# MilliToney.net
KiCad netlist of a schematic drawn in EAGLE
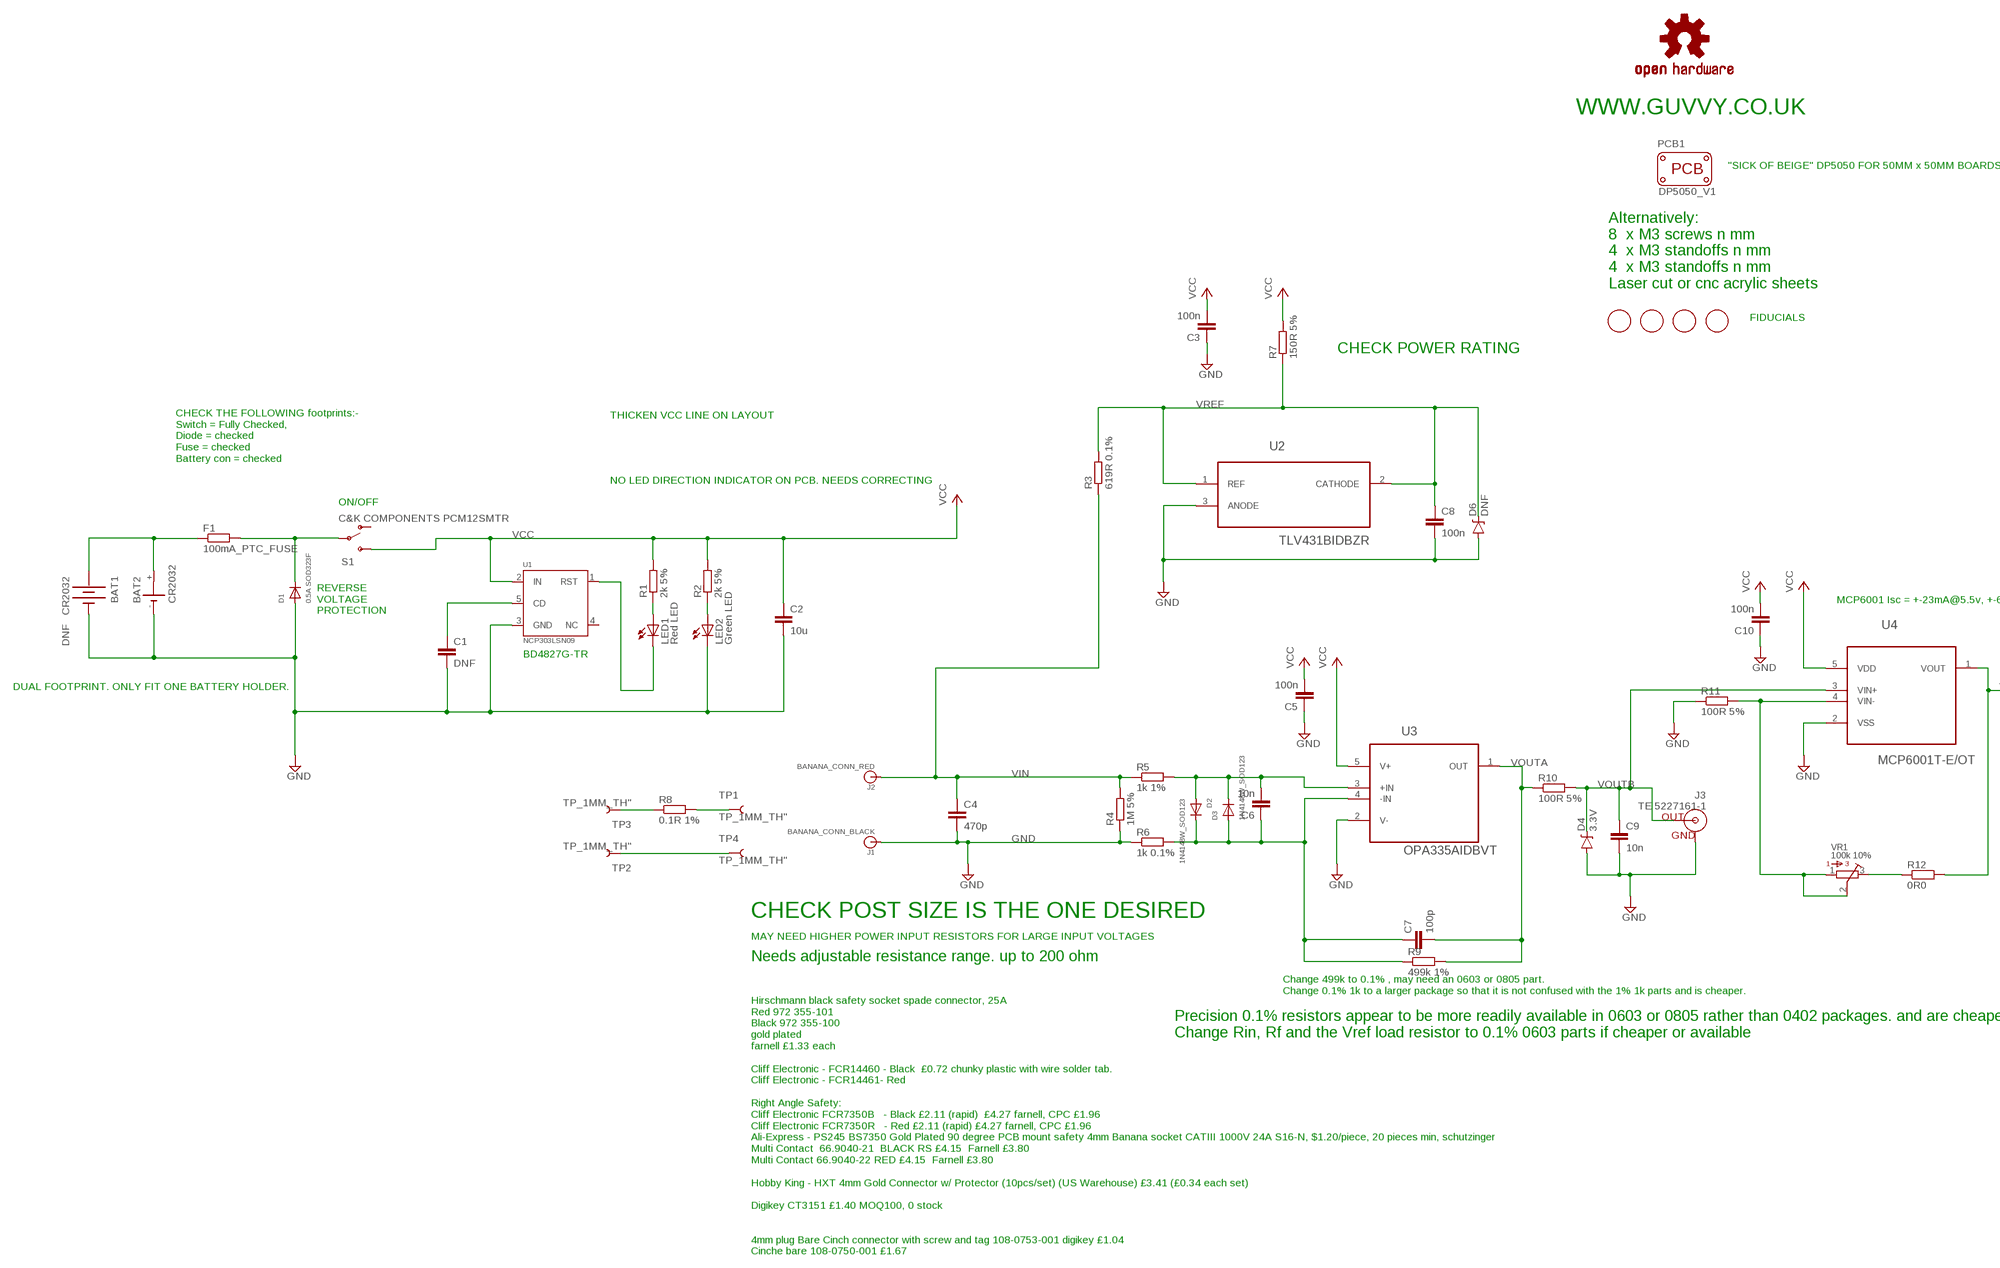
[diagram p0: schematic, sheet 1, part 1 of 2]
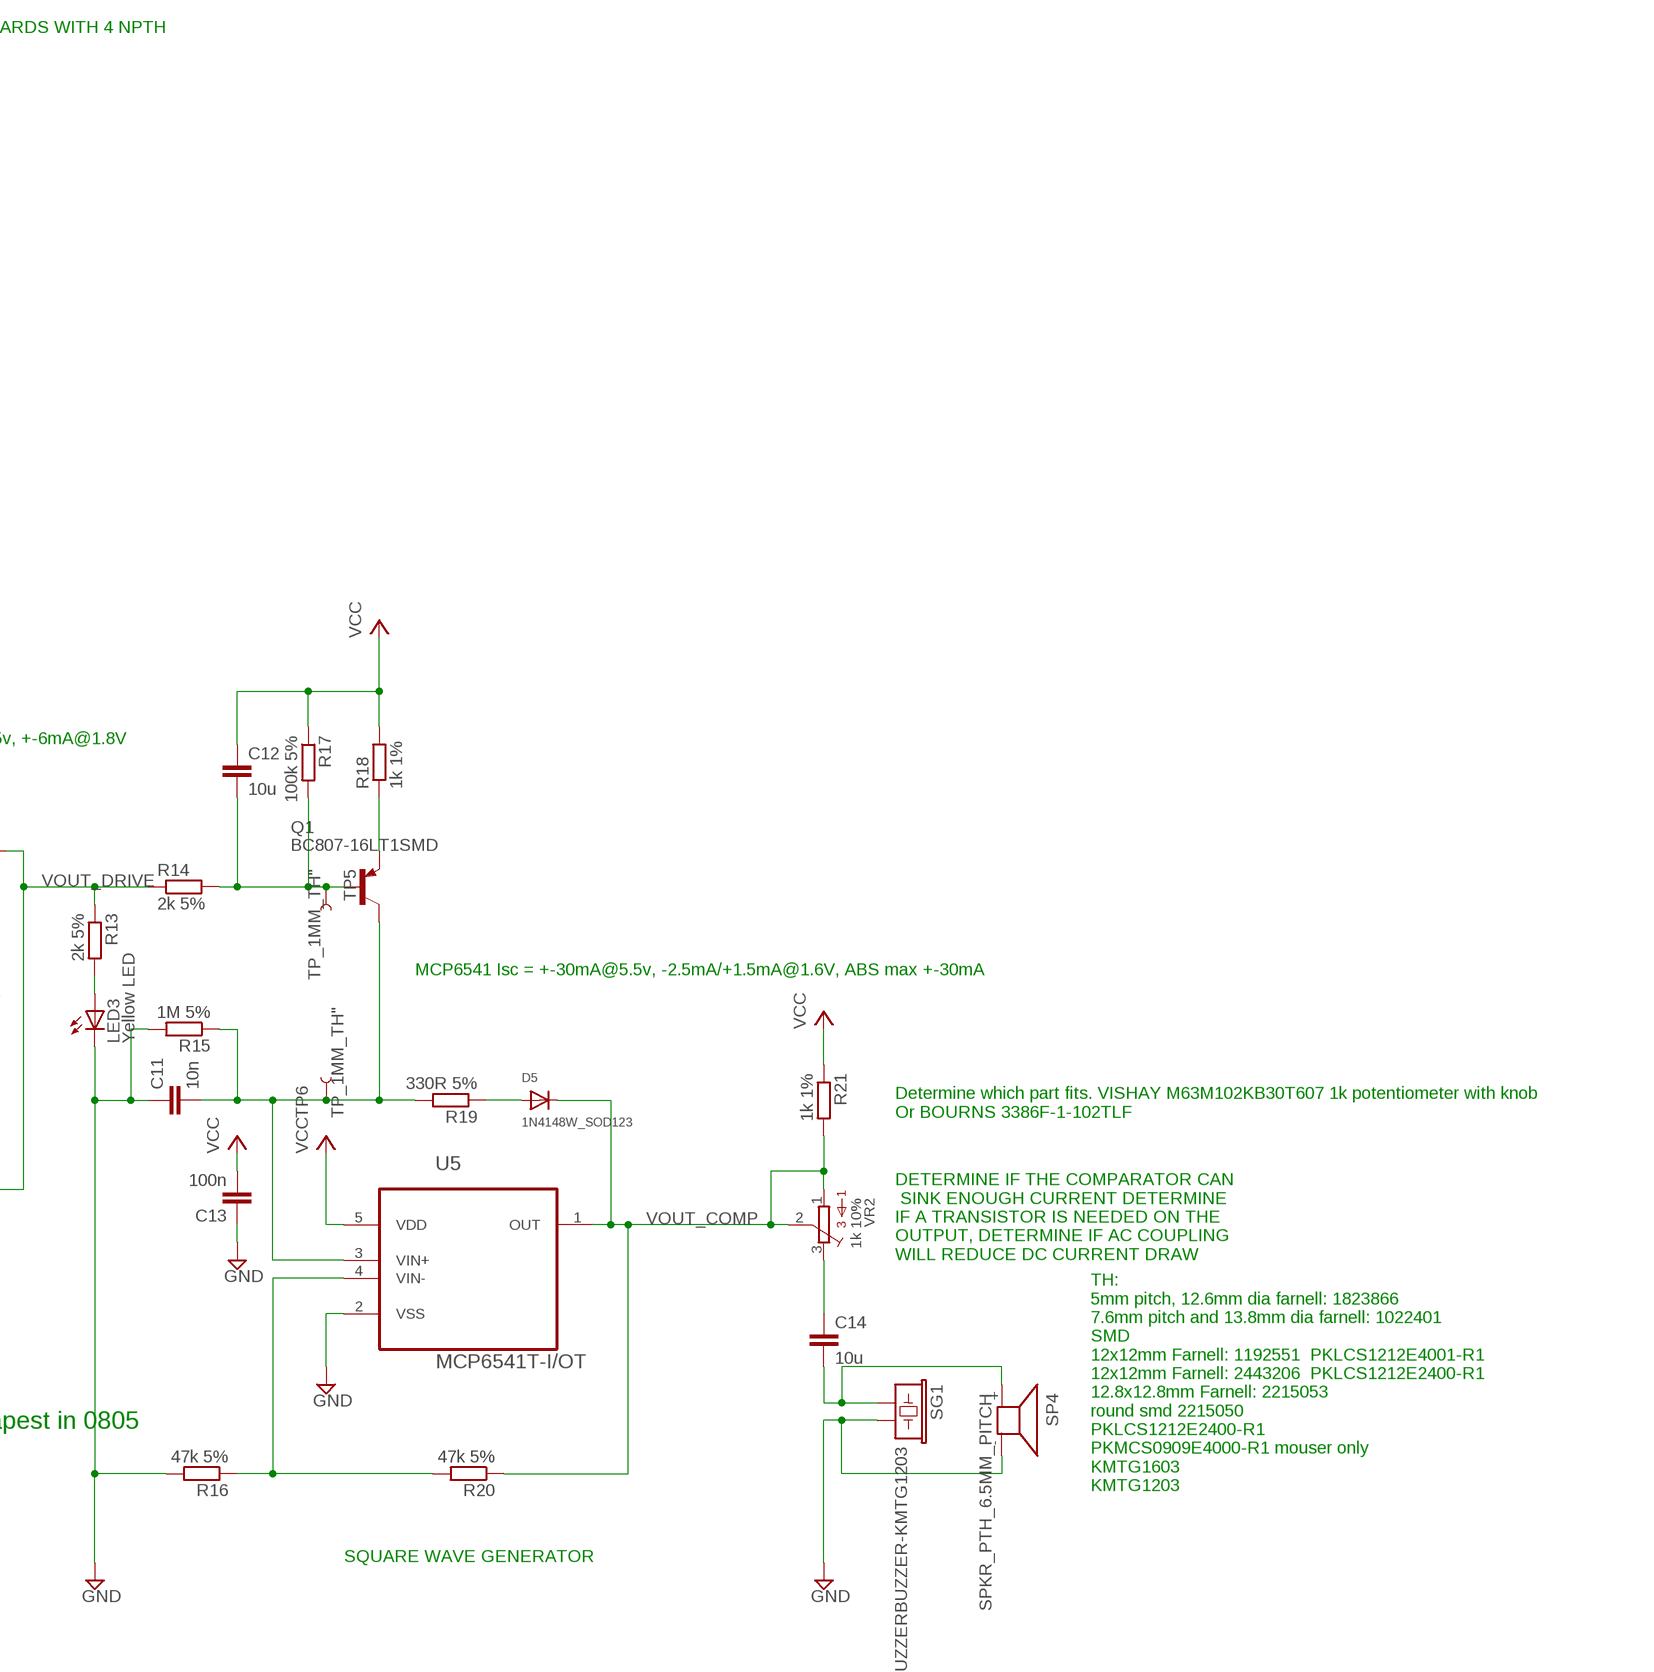
[diagram p1: schematic, sheet 1, part 2 of 2]

(export (version "E")
  (design (tool "Eeschema 10.0.6"))
  (components
    (comp (ref "BAT1")
      (value "DNF CR2032")
      (footprint "eagle-import:BATTERY_20MM_PTH_COMPACT")
      (libsource (lib "eagle-import") (part "BATTERYFOB"))
    )
    (comp (ref "BAT2")
      (value "CR2032")
      (footprint "eagle-import:KZH20SMD")
      (fields (field (name "MF") "RENATA") (field (name "MPN") "SMTU 2032-LF"))
      (libsource (lib "eagle-import") (part "2032"))
    )
    (comp (ref "C1")
      (value "DNF")
      (footprint "eagle-import:C0402K")
      (libsource (lib "eagle-import") (part "C-EUC0402K"))
    )
    (comp (ref "C2")
      (value "10u")
      (footprint "eagle-import:C0603")
      (fields (field (name "MF") "MURATA") (field (name "MPN") "GRM188R61A106ME69D"))
      (libsource (lib "eagle-import") (part "C-EUC0603"))
    )
    (comp (ref "C3")
      (value "100n")
      (footprint "eagle-import:C0402K")
      (fields (field (name "MF") "MULTICOMP") (field (name "MPN") "MC0402X104K100CT"))
      (libsource (lib "eagle-import") (part "C-EUC0402K"))
    )
    (comp (ref "C4")
      (value "470p")
      (footprint "eagle-import:C0402K")
      (libsource (lib "eagle-import") (part "C-EUC0402K"))
    )
    (comp (ref "C5")
      (value "100n")
      (footprint "eagle-import:C0402K")
      (fields (field (name "MF") "MULTICOMP") (field (name "MPN") "MC0402X104K100CT"))
      (libsource (lib "eagle-import") (part "C-EUC0402K"))
    )
    (comp (ref "C6")
      (value "10n")
      (footprint "eagle-import:C0402K")
      (libsource (lib "eagle-import") (part "C-EUC0402K"))
    )
    (comp (ref "C7")
      (value "100p")
      (footprint "eagle-import:C0402K")
      (libsource (lib "eagle-import") (part "C-EUC0402K"))
    )
    (comp (ref "C8")
      (value "100n")
      (footprint "eagle-import:C0402K")
      (fields (field (name "MF") "MULTICOMP") (field (name "MPN") "MC0402X104K100CT"))
      (libsource (lib "eagle-import") (part "C-EUC0402K"))
    )
    (comp (ref "C9")
      (value "10n")
      (footprint "eagle-import:C0402K")
      (libsource (lib "eagle-import") (part "C-EUC0402K"))
    )
    (comp (ref "C10")
      (value "100n")
      (footprint "eagle-import:C0402K")
      (fields (field (name "MF") "MULTICOMP") (field (name "MPN") "MC0402X104K100CT"))
      (libsource (lib "eagle-import") (part "C-EUC0402K"))
    )
    (comp (ref "C11")
      (value "10n")
      (footprint "eagle-import:C0402K")
      (libsource (lib "eagle-import") (part "C-EUC0402K"))
    )
    (comp (ref "C12")
      (value "10u")
      (footprint "eagle-import:C0603")
      (fields (field (name "MF") "MURATA") (field (name "MPN") "GRM188R61A106ME69D"))
      (libsource (lib "eagle-import") (part "C-EUC0603"))
    )
    (comp (ref "C13")
      (value "100n")
      (footprint "eagle-import:C0402K")
      (fields (field (name "MF") "MULTICOMP") (field (name "MPN") "MC0402X104K100CT"))
      (libsource (lib "eagle-import") (part "C-EUC0402K"))
    )
    (comp (ref "C14")
      (value "10u")
      (footprint "eagle-import:C0603K")
      (fields (field (name "MF") "MURATA") (field (name "MPN") "GRM188R61A106ME69D"))
      (libsource (lib "eagle-import") (part "C-EUC0603K"))
    )
    (comp (ref "D1")
      (value "0.5A SOD323F")
      (footprint "eagle-import:SOD-323F")
      (fields (field (name "MF") "NXP") (field (name "MPN") "PMEG3010EJ,115"))
      (libsource (lib "eagle-import") (part "DIODESOD-323F"))
    )
    (comp (ref "D2")
      (value "1N4148W_SOD123")
      (footprint "eagle-import:SOD-123FL")
      (fields (field (name "MF") "MULTICOMP") (field (name "MPN") "1N4148W"))
      (libsource (lib "eagle-import") (part "DIODE_SOD-123FL"))
    )
    (comp (ref "D3")
      (value "1N4148W_SOD123")
      (footprint "eagle-import:SOD-123FL")
      (fields (field (name "MF") "MULTICOMP") (field (name "MPN") "1N4148W"))
      (libsource (lib "eagle-import") (part "DIODE_SOD-123FL"))
    )
    (comp (ref "D4")
      (value "3.3V")
      (footprint "eagle-import:SOD-323")
      (libsource (lib "eagle-import") (part "DIODE-ZENER3.3V"))
    )
    (comp (ref "D5")
      (value "1N4148W_SOD123")
      (footprint "eagle-import:SOD-123FL")
      (fields (field (name "MF") "MULTICOMP") (field (name "MPN") "1N4148W"))
      (libsource (lib "eagle-import") (part "DIODE_SOD-123FL"))
    )
    (comp (ref "D6")
      (value "DNF")
      (footprint "eagle-import:SOD-323")
      (libsource (lib "eagle-import") (part "DIODE-ZENER3.3V"))
    )
    (comp (ref "F1")
      (value "100mA_PTC_FUSE")
      (footprint "eagle-import:R0805")
      (fields (field (name "MF") "BOURNS") (field (name "MPN") "MF-PSMF010X-2"))
      (libsource (lib "eagle-import") (part "R-EU_R0805"))
    )
    (comp (ref "FID1")
      (value "FIDUCIAL")
      (footprint "eagle-import:FIDUCIAL_1MM")
      (libsource (lib "eagle-import") (part "FIDUCIAL"))
    )
    (comp (ref "FID2")
      (value "FIDUCIAL")
      (footprint "eagle-import:FIDUCIAL_1MM")
      (libsource (lib "eagle-import") (part "FIDUCIAL"))
    )
    (comp (ref "FID3")
      (value "FIDUCIAL")
      (footprint "eagle-import:FIDUCIAL_1MM")
      (libsource (lib "eagle-import") (part "FIDUCIAL"))
    )
    (comp (ref "FID4")
      (value "FIDUCIAL")
      (footprint "eagle-import:FIDUCIAL_1MM")
      (libsource (lib "eagle-import") (part "FIDUCIAL"))
    )
    (comp (ref "J1")
      (value "BANANA_CONN_BLACK")
      (footprint "eagle-import:BANANA_CONN")
      (fields (field (name "MF") "CLIFF ELECTRONIC COMPONENTS") (field (name "MPN") "FCR14460"))
      (libsource (lib "eagle-import") (part "BANANA_CONN"))
    )
    (comp (ref "J2")
      (value "BANANA_CONN_RED")
      (footprint "eagle-import:BANANA_CONN")
      (fields (field (name "MF") "CLIFF ELECTRONIC COMPONENTS") (field (name "MPN") "FCR14461"))
      (libsource (lib "eagle-import") (part "BANANA_CONN"))
    )
    (comp (ref "J3")
      (value "TE 5227161-1")
      (footprint "eagle-import:BNC")
      (fields (field (name "MF") "TE CONNECTIVITY / AMP") (field (name "MPN") "5227161-1"))
      (libsource (lib "eagle-import") (part "BNCPTH"))
    )
    (comp (ref "LED1")
      (value "Red LED")
      (footprint "eagle-import:SML0603")
      (fields (field (name "MF") "KINGBRIGHT") (field (name "MPN") "KP-1608SURCK"))
      (libsource (lib "eagle-import") (part "LEDSML0603"))
    )
    (comp (ref "LED2")
      (value "Green LED")
      (footprint "eagle-import:SML0603")
      (fields (field (name "MF") "KINGBRIGHT") (field (name "MPN") "KP-1608CGCK"))
      (libsource (lib "eagle-import") (part "LEDSML0603"))
    )
    (comp (ref "LED3")
      (value "Yellow LED")
      (footprint "eagle-import:SML0603")
      (fields (field (name "MF") "KINGBRIGHT") (field (name "MPN") "KP-1608SYCK"))
      (libsource (lib "eagle-import") (part "LEDSML0603"))
    )
    (comp (ref "LOGO1")
      (value "OSHW-LOGOL")
      (footprint "eagle-import:OSHW-LOGO-L")
      (libsource (lib "eagle-import") (part "OSHW-LOGOL"))
    )
    (comp (ref "PCB1")
      (value "PCB_DP_SQUARE-5X5")
      (footprint "eagle-import:DP5050_V1")
      (libsource (lib "eagle-import") (part "PCB_DP_SQUARE-5X5"))
    )
    (comp (ref "Q1")
      (value "BC807-16LT1SMD")
      (footprint "eagle-import:SOT23-BEC")
      (fields (field (name "MF") "ON SEMICONDUCTOR") (field (name "MPN") "BC807-16LT1G"))
      (libsource (lib "eagle-import") (part "BC807SMD-16LT1"))
    )
    (comp (ref "R1")
      (value "2k 5%")
      (footprint "eagle-import:R0402")
      (libsource (lib "eagle-import") (part "R-EU_R0402"))
    )
    (comp (ref "R2")
      (value "2k 5%")
      (footprint "eagle-import:R0402")
      (libsource (lib "eagle-import") (part "R-EU_R0402"))
    )
    (comp (ref "R3")
      (value "619R 0.1%")
      (footprint "eagle-import:R0402")
      (fields (field (name "MF") "TE CONNECTIVITY") (field (name "MPN") "CPF0402B619RE1"))
      (libsource (lib "eagle-import") (part "R-EU_R0402"))
    )
    (comp (ref "R4")
      (value "1M 5%")
      (footprint "eagle-import:R0402")
      (libsource (lib "eagle-import") (part "R-EU_R0402"))
    )
    (comp (ref "R5")
      (value "1k 1%")
      (footprint "eagle-import:R0402")
      (libsource (lib "eagle-import") (part "R-EU_R0402"))
    )
    (comp (ref "R6")
      (value "1k 0.1%")
      (footprint "eagle-import:R0402")
      (fields (field (name "MF") "WELWYN") (field (name "MPN") "PCF0402-R-1K-B-T1."))
      (libsource (lib "eagle-import") (part "R-EU_R0402"))
    )
    (comp (ref "R7")
      (value "150R 5%")
      (footprint "eagle-import:R0402")
      (libsource (lib "eagle-import") (part "R-EU_R0402"))
    )
    (comp (ref "R8")
      (value "0.1R 1%")
      (footprint "eagle-import:R0603")
      (fields (field (name "MF") "PANASONIC ELECTRONIC COMPONENTS") (field (name "MPN") "ERJ3RSFR10V"))
      (libsource (lib "eagle-import") (part "R-EU_R0603"))
    )
    (comp (ref "R9")
      (value "499k 1%")
      (footprint "eagle-import:R0402")
      (fields (field (name "MF") "PANASONIC ELECTRONIC COMPONENTS") (field (name "MPN") "ERJ3EKF4993V"))
      (libsource (lib "eagle-import") (part "R-EU_R0402"))
    )
    (comp (ref "R10")
      (value "100R 5%")
      (footprint "eagle-import:R0402")
      (libsource (lib "eagle-import") (part "R-EU_R0402"))
    )
    (comp (ref "R11")
      (value "100R 5%")
      (footprint "eagle-import:R0402")
      (libsource (lib "eagle-import") (part "R-EU_R0402"))
    )
    (comp (ref "R12")
      (value "0R0")
      (footprint "eagle-import:R0402")
      (libsource (lib "eagle-import") (part "R-EU_R0402"))
    )
    (comp (ref "R13")
      (value "2k 5%")
      (footprint "eagle-import:R0402")
      (libsource (lib "eagle-import") (part "R-EU_R0402"))
    )
    (comp (ref "R14")
      (value "2k 5%")
      (footprint "eagle-import:R0402")
      (libsource (lib "eagle-import") (part "R-EU_R0402"))
    )
    (comp (ref "R15")
      (value "1M 5%")
      (footprint "eagle-import:R0402")
      (libsource (lib "eagle-import") (part "R-EU_R0402"))
    )
    (comp (ref "R16")
      (value "47k 5%")
      (footprint "eagle-import:R0402")
      (libsource (lib "eagle-import") (part "R-EU_R0402"))
    )
    (comp (ref "R17")
      (value "100k 5%")
      (footprint "eagle-import:R0402")
      (libsource (lib "eagle-import") (part "R-EU_R0402"))
    )
    (comp (ref "R18")
      (value "1k 1%")
      (footprint "eagle-import:R0402")
      (libsource (lib "eagle-import") (part "R-EU_R0402"))
    )
    (comp (ref "R19")
      (value "330R 5%")
      (footprint "eagle-import:R0402")
      (libsource (lib "eagle-import") (part "R-EU_R0402"))
    )
    (comp (ref "R20")
      (value "47k 5%")
      (footprint "eagle-import:R0402")
      (libsource (lib "eagle-import") (part "R-EU_R0402"))
    )
    (comp (ref "R21")
      (value "1k 1%")
      (footprint "eagle-import:R0402")
      (libsource (lib "eagle-import") (part "R-EU_R0402"))
    )
    (comp (ref "S1")
      (value "C&K COMPONENTS PCM12SMTR")
      (footprint "eagle-import:SWITCH-SPST-SMD-A")
      (fields (field (name "MF") "C & K COMPONENTS") (field (name "MPN") "PCM12SMTR"))
      (libsource (lib "eagle-import") (part "SWITCH-SPDT-SMD-A"))
    )
    (comp (ref "SG1")
      (value "BUZZERBUZZER-KMTG1203")
      (footprint "eagle-import:BUZZER-KMTG1203")
      (fields (field (name "MF") "KINGSTATE") (field (name "MPN") "KMTG1203"))
      (libsource (lib "eagle-import") (part "BUZZERBUZZER-KMTG1203"))
    )
    (comp (ref "SP4")
      (value "SPKR_PTH_6.5MM_PITCH")
      (footprint "eagle-import:KSS1201")
      (libsource (lib "eagle-import") (part "KSS1201"))
    )
    (comp (ref "TP1")
      (value "TP_1MM_TH\"")
      (footprint "eagle-import:TP_1MM_TH")
      (libsource (lib "eagle-import") (part "TP_1MM_TH{dblquote}"))
    )
    (comp (ref "TP2")
      (value "TP_1MM_TH\"")
      (footprint "eagle-import:TP_1MM_TH")
      (libsource (lib "eagle-import") (part "TP_1MM_TH{dblquote}"))
    )
    (comp (ref "TP3")
      (value "TP_1MM_TH\"")
      (footprint "eagle-import:TP_1MM_TH")
      (libsource (lib "eagle-import") (part "TP_1MM_TH{dblquote}"))
    )
    (comp (ref "TP4")
      (value "TP_1MM_TH\"")
      (footprint "eagle-import:TP_1MM_TH")
      (libsource (lib "eagle-import") (part "TP_1MM_TH{dblquote}"))
    )
    (comp (ref "TP5")
      (value "TP_1MM_TH\"")
      (footprint "eagle-import:TP_1MM_TH")
      (libsource (lib "eagle-import") (part "TP_1MM_TH{dblquote}"))
    )
    (comp (ref "TP6")
      (value "TP_1MM_TH\"")
      (footprint "eagle-import:TP_1MM_TH")
      (libsource (lib "eagle-import") (part "TP_1MM_TH{dblquote}"))
    )
    (comp (ref "U1")
      (value "NCP303LSN09")
      (footprint "eagle-import:SOT23-5")
      (fields (field (name "MF") "ROHM") (field (name "MPN") "BD4827G-TR"))
      (libsource (lib "eagle-import") (part "NCP303LSN09"))
    )
    (comp (ref "U2")
      (value "TLV431BIDBZR")
      (footprint "eagle-import:SOT95P237X112-3N")
      (fields
        (field (name "MF") "TEXAS INSTRUMENTS")
        (field (name "MPN") "TLV431BCDBZTG4")
        (field (name "OC_FARNELL") "1053385")
      )
      (libsource (lib "eagle-import") (part "TLV431BIDBZR"))
    )
    (comp (ref "U3")
      (value "OPA335AIDBVT")
      (footprint "eagle-import:SOT95P280X145-5N")
      (fields (field (name "MF") "TEXAS INSTRUMENTS"))
      (libsource (lib "eagle-import") (part "OPA335AIDBVT"))
    )
    (comp (ref "U4")
      (value "MCP6001T-E/OT")
      (footprint "eagle-import:SOT95P270X145-5N")
      (fields (field (name "MF") "MICROCHIP"))
      (libsource (lib "eagle-import") (part "MCP6001T-E/OT"))
    )
    (comp (ref "U5")
      (value "MCP6541T-I/OT")
      (footprint "eagle-import:SOT95P290X145-5N")
      (fields (field (name "MF") "MICROCHIP"))
      (libsource (lib "eagle-import") (part "MCP6541T-I/OT"))
    )
    (comp (ref "VR1")
      (value "100k 10%")
      (footprint "eagle-import:3386F")
      (fields (field (name "MF") "BOURNS") (field (name "MPN") "3386F-1-104TLF"))
      (libsource (lib "eagle-import") (part "3386-F"))
    )
    (comp (ref "VR2")
      (value "1k 10%")
      (footprint "eagle-import:3386F")
      (fields (field (name "MF") "BOURNS") (field (name "MPN") "3386F-1-102TLF"))
      (libsource (lib "eagle-import") (part "3386-F"))
    )
  )
  (nets
    (net (code "1") (name "/VIN") (class "Default")
      (node (ref "C4") (pin "1") (pinfunction "1_1") (pintype "passive"))
      (node (ref "J2") (pin "P$1") (pinfunction "1_P$1") (pintype "passive"))
      (node (ref "R3") (pin "1") (pinfunction "1_1") (pintype "passive"))
      (node (ref "R4") (pin "2") (pinfunction "2_2") (pintype "passive"))
      (node (ref "R5") (pin "1") (pinfunction "1_1") (pintype "passive"))
    )
    (net (code "2") (name "/VOUTA") (class "Default")
      (node (ref "C7") (pin "2") (pinfunction "2_2") (pintype "passive"))
      (node (ref "R10") (pin "1") (pinfunction "1_1") (pintype "passive"))
      (node (ref "R9") (pin "2") (pinfunction "2_2") (pintype "passive"))
      (node (ref "U3") (pin "1") (pinfunction "OUT_1") (pintype "output"))
    )
    (net (code "3") (name "/VOUTB") (class "Default")
      (node (ref "C9") (pin "1") (pinfunction "1_1") (pintype "passive"))
      (node (ref "D4") (pin "C") (pinfunction "C_C") (pintype "passive"))
      (node (ref "J3") (pin "S") (pinfunction "OUT_S") (pintype "bidirectional"))
      (node (ref "R10") (pin "2") (pinfunction "2_2") (pintype "passive"))
      (node (ref "U4") (pin "3") (pinfunction "VIN+_3") (pintype "input"))
    )
    (net (code "4") (name "/VOUT_COMP") (class "Default")
      (node (ref "D5") (pin "C") (pinfunction "C_C") (pintype "passive"))
      (node (ref "R20") (pin "1") (pinfunction "1_1") (pintype "passive"))
      (node (ref "R21") (pin "2") (pinfunction "2_2") (pintype "passive"))
      (node (ref "U5") (pin "1") (pinfunction "OUT_1") (pintype "output"))
      (node (ref "VR2") (pin "1") (pinfunction "1_1") (pintype "passive"))
      (node (ref "VR2") (pin "2") (pinfunction "2_2") (pintype "passive"))
    )
    (net (code "5") (name "/VOUT_DRIVE") (class "Default")
      (node (ref "R12") (pin "2") (pinfunction "2_2") (pintype "passive"))
      (node (ref "R13") (pin "1") (pinfunction "1_1") (pintype "passive"))
      (node (ref "R14") (pin "1") (pinfunction "1_1") (pintype "passive"))
      (node (ref "U4") (pin "1") (pinfunction "VOUT_1") (pintype "output"))
    )
    (net (code "6") (name "/VREF") (class "Default")
      (node (ref "C8") (pin "1") (pinfunction "1_1") (pintype "passive"))
      (node (ref "D6") (pin "C") (pinfunction "C_C") (pintype "passive"))
      (node (ref "R3") (pin "2") (pinfunction "2_2") (pintype "passive"))
      (node (ref "R7") (pin "1") (pinfunction "1_1") (pintype "passive"))
      (node (ref "U2") (pin "1") (pinfunction "REF_1") (pintype "passive"))
      (node (ref "U2") (pin "2") (pinfunction "CATHODE_2") (pintype "output"))
    )
    (net (code "7") (name "GND") (class "Default")
      (node (ref "BAT1") (pin "2") (pinfunction "-_2") (pintype "power_in"))
      (node (ref "BAT2") (pin "-") (pinfunction "-_-") (pintype "passive"))
      (node (ref "C1") (pin "2") (pinfunction "2_2") (pintype "passive"))
      (node (ref "C10") (pin "1") (pinfunction "1_1") (pintype "passive"))
      (node (ref "C11") (pin "1") (pinfunction "1_1") (pintype "passive"))
      (node (ref "C13") (pin "1") (pinfunction "1_1") (pintype "passive"))
      (node (ref "C2") (pin "2") (pinfunction "2_2") (pintype "passive"))
      (node (ref "C3") (pin "1") (pinfunction "1_1") (pintype "passive"))
      (node (ref "C4") (pin "2") (pinfunction "2_2") (pintype "passive"))
      (node (ref "C5") (pin "1") (pinfunction "1_1") (pintype "passive"))
      (node (ref "C8") (pin "2") (pinfunction "2_2") (pintype "passive"))
      (node (ref "C9") (pin "2") (pinfunction "2_2") (pintype "passive"))
      (node (ref "D1") (pin "A") (pinfunction "A_A") (pintype "passive"))
      (node (ref "D4") (pin "A") (pinfunction "A_A") (pintype "passive"))
      (node (ref "D6") (pin "A") (pinfunction "A_A") (pintype "passive"))
      (node (ref "J1") (pin "P$1") (pinfunction "1_P$1") (pintype "passive"))
      (node (ref "J3") (pin "GND") (pinfunction "GND_GND") (pintype "bidirectional"))
      (node (ref "LED2") (pin "C") (pinfunction "C_C") (pintype "passive"))
      (node (ref "LED3") (pin "C") (pinfunction "C_C") (pintype "passive"))
      (node (ref "R11") (pin "1") (pinfunction "1_1") (pintype "passive"))
      (node (ref "R15") (pin "2") (pinfunction "2_2") (pintype "passive"))
      (node (ref "R16") (pin "2") (pinfunction "2_2") (pintype "passive"))
      (node (ref "R4") (pin "1") (pinfunction "1_1") (pintype "passive"))
      (node (ref "R6") (pin "1") (pinfunction "1_1") (pintype "passive"))
      (node (ref "SG1") (pin "2") (pinfunction "2_2") (pintype "passive"))
      (node (ref "SP4") (pin "-") (pinfunction "2_-") (pintype "passive"))
      (node (ref "U1") (pin "3") (pinfunction "GND_3") (pintype "bidirectional"))
      (node (ref "U2") (pin "3") (pinfunction "ANODE_3") (pintype "input"))
      (node (ref "U3") (pin "2") (pinfunction "V-_2") (pintype "power_in"))
      (node (ref "U4") (pin "2") (pinfunction "VSS_2") (pintype "passive"))
      (node (ref "U5") (pin "2") (pinfunction "VSS_2") (pintype "power_in"))
    )
    (net (code "8") (name "Net-(BAT1-+)") (class "Default")
      (node (ref "BAT1") (pin "1") (pinfunction "+_1") (pintype "power_in"))
      (node (ref "BAT2") (pin "+") (pinfunction "+_+") (pintype "passive"))
      (node (ref "F1") (pin "1") (pinfunction "1_1") (pintype "passive"))
    )
    (net (code "9") (name "Net-(C14-Pad1)") (class "Default")
      (node (ref "C14") (pin "1") (pinfunction "1_1") (pintype "passive"))
      (node (ref "VR2") (pin "3") (pinfunction "3_3") (pintype "passive"))
    )
    (net (code "10") (name "Net-(D5-PadA)") (class "Default")
      (node (ref "D5") (pin "A") (pinfunction "A_A") (pintype "passive"))
      (node (ref "R19") (pin "1") (pinfunction "1_1") (pintype "passive"))
    )
    (net (code "11") (name "Net-(LED1-PadA)") (class "Default")
      (node (ref "LED1") (pin "A") (pinfunction "A_A") (pintype "passive"))
      (node (ref "R1") (pin "1") (pinfunction "1_1") (pintype "passive"))
    )
    (net (code "12") (name "Net-(LED2-PadA)") (class "Default")
      (node (ref "LED2") (pin "A") (pinfunction "A_A") (pintype "passive"))
      (node (ref "R2") (pin "1") (pinfunction "1_1") (pintype "passive"))
    )
    (net (code "13") (name "Net-(LED3-PadA)") (class "Default")
      (node (ref "LED3") (pin "A") (pinfunction "A_A") (pintype "passive"))
      (node (ref "R13") (pin "2") (pinfunction "2_2") (pintype "passive"))
    )
    (net (code "14") (name "Net-(Q1-PadE)") (class "Default")
      (node (ref "Q1") (pin "E") (pinfunction "E_E") (pintype "passive"))
      (node (ref "R18") (pin "1") (pinfunction "1_1") (pintype "passive"))
    )
    (net (code "15") (name "Net-(R12-Pad1)") (class "Default")
      (node (ref "R12") (pin "1") (pinfunction "1_1") (pintype "passive"))
      (node (ref "VR1") (pin "3") (pinfunction "3_3") (pintype "passive"))
    )
    (net (code "16") (name "Net-(S1-P)") (class "Default")
      (node (ref "D1") (pin "C") (pinfunction "C_C") (pintype "passive"))
      (node (ref "F1") (pin "2") (pinfunction "2_2") (pintype "passive"))
      (node (ref "S1") (pin "2") (pinfunction "P_2") (pintype "passive"))
    )
    (net (code "17") (name "Net-(SP4-1)") (class "Default")
      (node (ref "C14") (pin "2") (pinfunction "2_2") (pintype "passive"))
      (node (ref "SG1") (pin "1") (pinfunction "1_1") (pintype "passive"))
      (node (ref "SP4") (pin "+") (pinfunction "1_+") (pintype "passive"))
    )
    (net (code "18") (name "Net-(TP1-1)") (class "Default")
      (node (ref "R8") (pin "2") (pinfunction "2_2") (pintype "passive"))
      (node (ref "TP1") (pin "P$1") (pinfunction "1_P$1") (pintype "bidirectional"))
    )
    (net (code "19") (name "Net-(TP2-1)") (class "Default")
      (node (ref "TP2") (pin "P$1") (pinfunction "1_P$1") (pintype "bidirectional"))
      (node (ref "TP4") (pin "P$1") (pinfunction "1_P$1") (pintype "bidirectional"))
    )
    (net (code "20") (name "Net-(TP3-1)") (class "Default")
      (node (ref "R8") (pin "1") (pinfunction "1_1") (pintype "passive"))
      (node (ref "TP3") (pin "P$1") (pinfunction "1_P$1") (pintype "bidirectional"))
    )
    (net (code "21") (name "Net-(TP5-1)") (class "Default")
      (node (ref "C12") (pin "2") (pinfunction "2_2") (pintype "passive"))
      (node (ref "Q1") (pin "B") (pinfunction "B_B") (pintype "passive"))
      (node (ref "R14") (pin "2") (pinfunction "2_2") (pintype "passive"))
      (node (ref "R17") (pin "2") (pinfunction "2_2") (pintype "passive"))
      (node (ref "TP5") (pin "P$1") (pinfunction "1_P$1") (pintype "bidirectional"))
    )
    (net (code "22") (name "Net-(TP6-1)") (class "Default")
      (node (ref "C11") (pin "2") (pinfunction "2_2") (pintype "passive"))
      (node (ref "Q1") (pin "C") (pinfunction "C_C") (pintype "passive"))
      (node (ref "R15") (pin "1") (pinfunction "1_1") (pintype "passive"))
      (node (ref "R19") (pin "2") (pinfunction "2_2") (pintype "passive"))
      (node (ref "TP6") (pin "P$1") (pinfunction "1_P$1") (pintype "bidirectional"))
      (node (ref "U5") (pin "3") (pinfunction "VIN+_3") (pintype "input"))
    )
    (net (code "23") (name "Net-(U1-CD)") (class "Default")
      (node (ref "C1") (pin "1") (pinfunction "1_1") (pintype "passive"))
      (node (ref "U1") (pin "5") (pinfunction "CD_5") (pintype "bidirectional"))
    )
    (net (code "24") (name "Net-(U1-RST)") (class "Default")
      (node (ref "LED1") (pin "C") (pinfunction "C_C") (pintype "passive"))
      (node (ref "U1") (pin "1") (pinfunction "RST_1") (pintype "bidirectional"))
    )
    (net (code "25") (name "Net-(U3-+IN)") (class "Default")
      (node (ref "C6") (pin "2") (pinfunction "2_2") (pintype "passive"))
      (node (ref "D2") (pin "A") (pinfunction "A_A") (pintype "passive"))
      (node (ref "D3") (pin "C") (pinfunction "C_C") (pintype "passive"))
      (node (ref "R5") (pin "2") (pinfunction "2_2") (pintype "passive"))
      (node (ref "U3") (pin "3") (pinfunction "+IN_3") (pintype "input"))
    )
    (net (code "26") (name "Net-(U3--IN)") (class "Default")
      (node (ref "C6") (pin "1") (pinfunction "1_1") (pintype "passive"))
      (node (ref "C7") (pin "1") (pinfunction "1_1") (pintype "passive"))
      (node (ref "D2") (pin "C") (pinfunction "C_C") (pintype "passive"))
      (node (ref "D3") (pin "A") (pinfunction "A_A") (pintype "passive"))
      (node (ref "R6") (pin "2") (pinfunction "2_2") (pintype "passive"))
      (node (ref "R9") (pin "1") (pinfunction "1_1") (pintype "passive"))
      (node (ref "U3") (pin "4") (pinfunction "-IN_4") (pintype "input"))
    )
    (net (code "27") (name "Net-(U4-VIN-)") (class "Default")
      (node (ref "R11") (pin "2") (pinfunction "2_2") (pintype "passive"))
      (node (ref "U4") (pin "4") (pinfunction "VIN-_4") (pintype "input"))
      (node (ref "VR1") (pin "1") (pinfunction "1_1") (pintype "passive"))
      (node (ref "VR1") (pin "2") (pinfunction "2_2") (pintype "passive"))
    )
    (net (code "28") (name "Net-(U5-VIN-)") (class "Default")
      (node (ref "R16") (pin "1") (pinfunction "1_1") (pintype "passive"))
      (node (ref "R20") (pin "2") (pinfunction "2_2") (pintype "passive"))
      (node (ref "U5") (pin "4") (pinfunction "VIN-_4") (pintype "input"))
    )
    (net (code "29") (name "VCC") (class "Default")
      (node (ref "C10") (pin "2") (pinfunction "2_2") (pintype "passive"))
      (node (ref "C12") (pin "1") (pinfunction "1_1") (pintype "passive"))
      (node (ref "C13") (pin "2") (pinfunction "2_2") (pintype "passive"))
      (node (ref "C2") (pin "1") (pinfunction "1_1") (pintype "passive"))
      (node (ref "C3") (pin "2") (pinfunction "2_2") (pintype "passive"))
      (node (ref "C5") (pin "2") (pinfunction "2_2") (pintype "passive"))
      (node (ref "R1") (pin "2") (pinfunction "2_2") (pintype "passive"))
      (node (ref "R17") (pin "1") (pinfunction "1_1") (pintype "passive"))
      (node (ref "R18") (pin "2") (pinfunction "2_2") (pintype "passive"))
      (node (ref "R2") (pin "2") (pinfunction "2_2") (pintype "passive"))
      (node (ref "R21") (pin "1") (pinfunction "1_1") (pintype "passive"))
      (node (ref "R7") (pin "2") (pinfunction "2_2") (pintype "passive"))
      (node (ref "S1") (pin "3") (pinfunction "S_3") (pintype "passive"))
      (node (ref "U1") (pin "2") (pinfunction "IN_2") (pintype "bidirectional"))
      (node (ref "U3") (pin "5") (pinfunction "V+_5") (pintype "power_in"))
      (node (ref "U4") (pin "5") (pinfunction "VDD_5") (pintype "power_in"))
      (node (ref "U5") (pin "5") (pinfunction "VDD_5") (pintype "power_in"))
    )
    (net (code "30") (name "unconnected-(S1-O-Pad1)") (class "Default")
      (node (ref "S1") (pin "1") (pinfunction "O_1") (pintype "passive"))
    )
    (net (code "31") (name "unconnected-(U1-NC-Pad4)") (class "Default")
      (node (ref "U1") (pin "4") (pinfunction "NC_4") (pintype "bidirectional"))
    )
  )
)
